# MIXR_Power_-_Battery_Management.net
KiCad netlist of a schematic drawn in Altium Designer
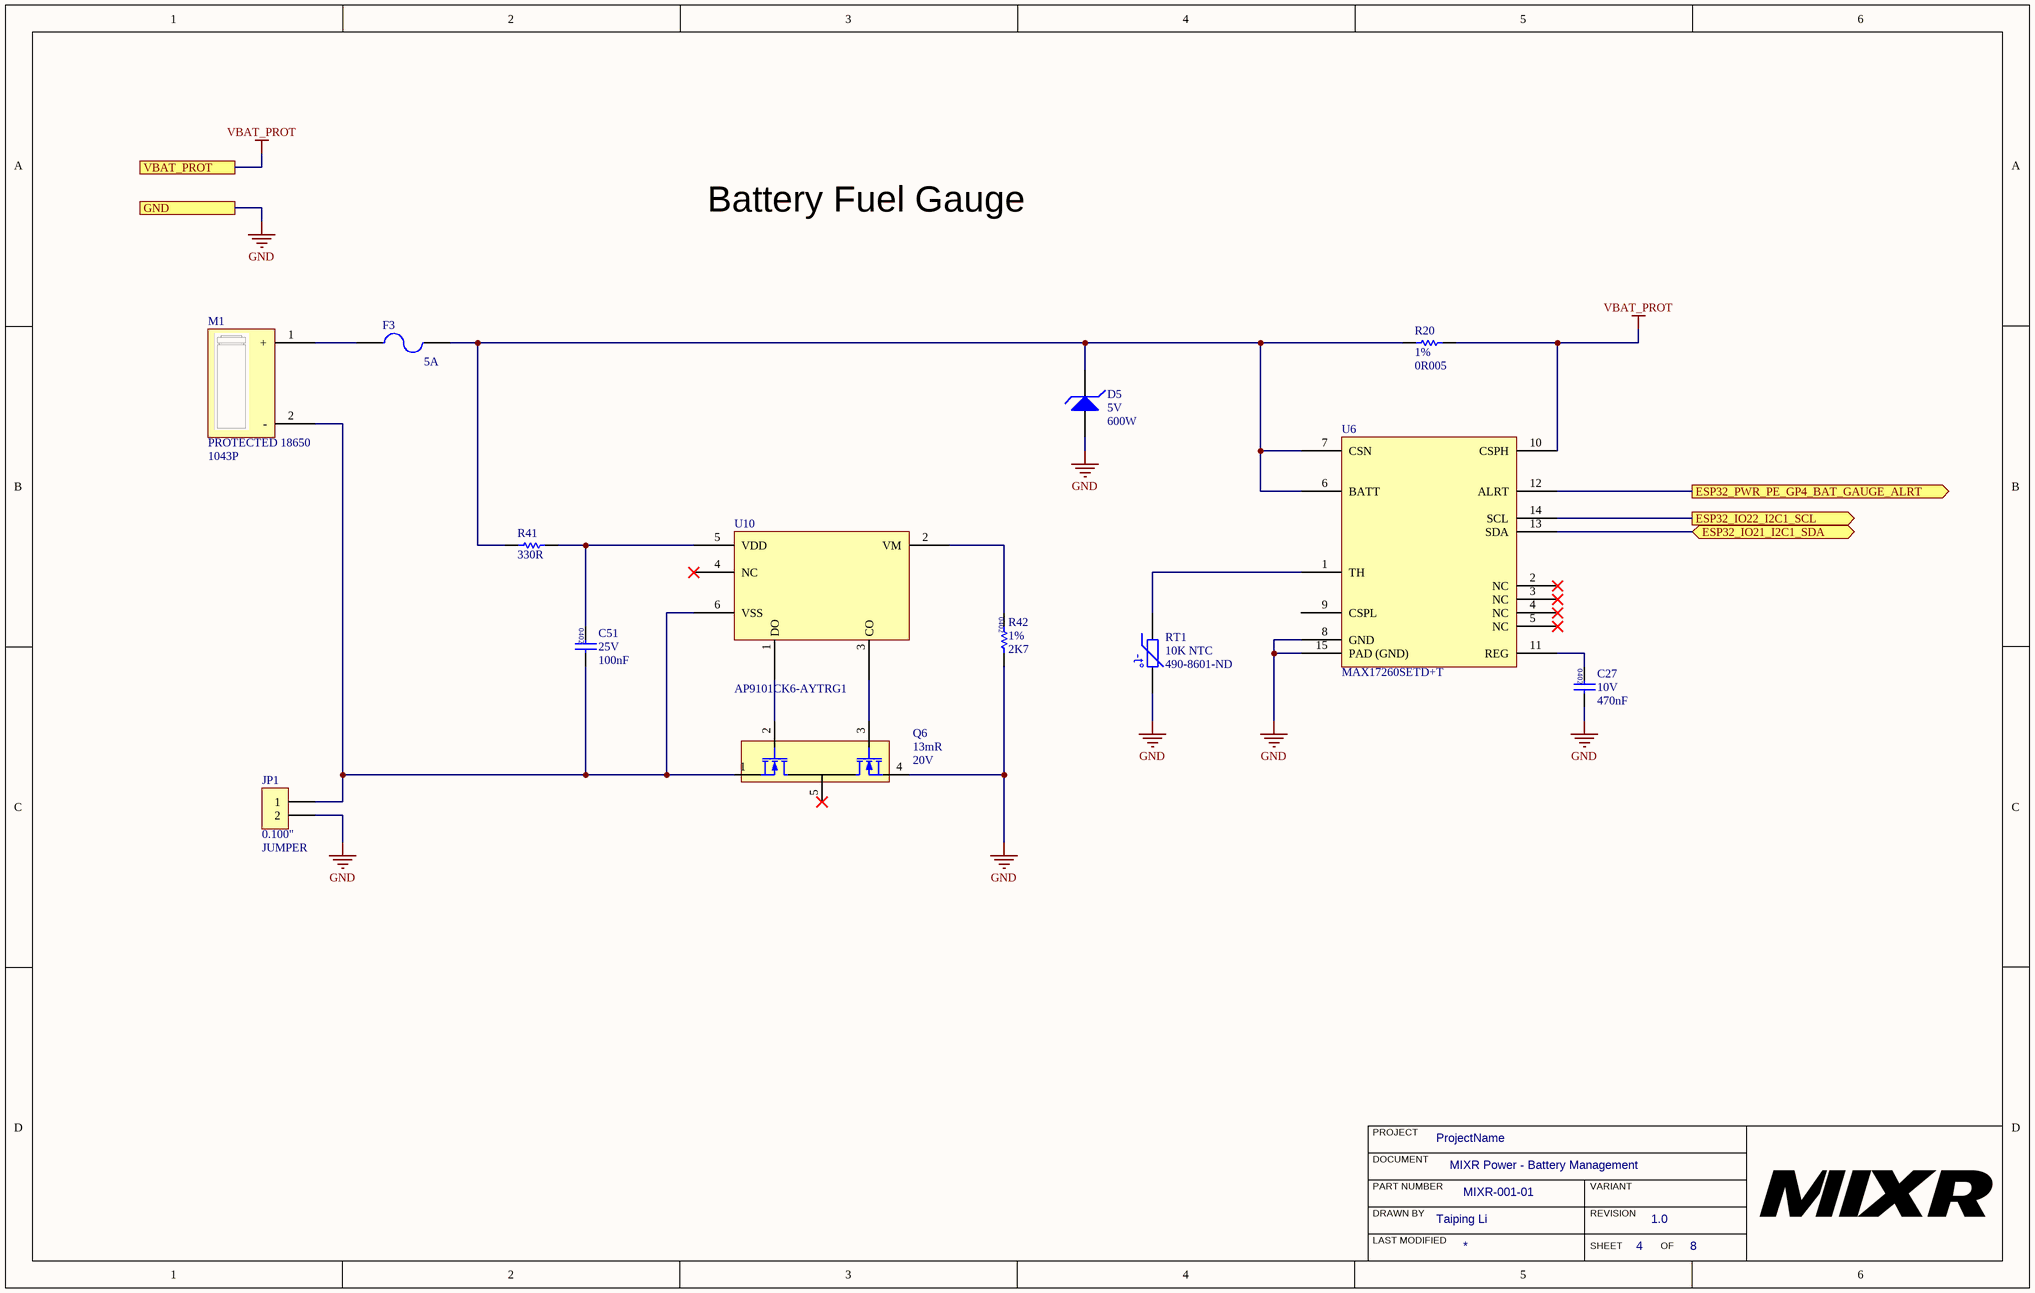
[diagram p0: MIXR Power - Battery Management.SchDoc]

(export (version "E")
  (design (tool "Eeschema 10.0.6"))
  (components
    (comp (ref "C27")
      (value "CAP CER 0.47UF 10V X7R 0402")
      (footprint "CAP 0402")
      (description "CAP ,MLCC ,0402,6.3V,X7R,0.47uF, 10% ,T&R;")
      (fields
        (field (name "MANUFACTURER") "Taiyo Yuden")
        (field (name "MANUFACTURER PART NUMBER") "LMK105B7474KV-F")
        (field (name "VOLTAGE RATING") "10V")
        (field (name "CAPACITANCE") "470nF")
      )
      (libsource (lib "Schematic Diagrams") (part "CAP CER 0.47UF 10V X7R 0402"))
    )
    (comp (ref "C51")
      (value "CAP CER 0.1UF 16V X7R 0402")
      (footprint "CAP 0402")
      (description "Cap Ceramic 0.1uF 25V X7R 10% SMD 0402 125C Paper T/R")
      (fields
        (field (name "MANUFACTURER") "Murata")
        (field (name "MANUFACTURER PART NUMBER") "GRM155R71E104KE14D")
        (field (name "VOLTAGE") "25V")
        (field (name "CAPACITANCE") "100nF")
      )
      (libsource (lib "Schematic Diagrams") (part "CAP CER 0.1UF 16V X7R 0402"))
    )
    (comp (ref "D5")
      (value "DIODE TVS 5VWM 9.1VC DO-214AA (SMB)")
      (footprint "DO-214AA Diode")
      (description "TVS DIODE 5V 9.1V DO214AA")
      (fields
        (field (name "MANUFACTURER") "Vishay Semiconductor Diodes Division")
        (field (name "MANUFACTURER PART NUMBER") "SMBJ5.0D-M3/H")
        (field (name "VOLTAGE - REVERSE STANDOFF (TYP)") "5V")
        (field (name "POWER - PEAK PULSE") "600W")
      )
      (libsource (lib "Schematic Diagrams") (part "DIODE TVS 5VWM 9.1VC DO-214AA (SMB)"))
    )
    (comp (ref "F3")
      (value "FUSE 5A 32VDC 1206")
      (footprint "FUSE LITTLEFUSE 0466 1206")
      (description "FUSE 5.0A 125VAC FAST 1206")
      (fields
        (field (name "MANUFACTURER") "Bel TRP")
        (field (name "MANUFACTURER PART NUMBER") "C1F5")
        (field (name "CURRENT RATING") "5A")
      )
      (libsource (lib "Schematic Diagrams") (part "FUSE 5A 32VDC 1206"))
    )
    (comp (ref "JP1")
      (value "JUMPER")
      (footprint "CONN, 2POS JUMPER 0.1\"")
      (description "2 Positions Header Connector Through Hole Gold")
      (fields
        (field (name "MANUFACTURER") "Omron Electronics Inc-EMC Div")
        (field (name "MANUFACTURER PART NUMBER") "XG8T-0231")
        (field (name "ROW SPACING - MATING") "0.100\"")
        (field (name "TYPE") "JUMPER")
      )
      (libsource (lib "Schematic Diagrams") (part "CONN 2POS JUMPER 0.1{dblquote}"))
    )
    (comp (ref "M1")
      (value "PROTECTED 18650")
      (footprint "BATTERY HOLDER 18650 PC PIN")
      (description "BATTERY HOLDER 18650 PC PIN")
      (fields
        (field (name "MANUFACTURER") "Keystone Electronics")
        (field (name "MANUFACTURER PART NUMBER") "1043P")
      )
      (libsource (lib "Schematic Diagrams") (part "BATTERY HOLDER 18650"))
    )
    (comp (ref "Q6")
      (value "MOSFET 2N-CH 20V 9A 6-UDFN")
      (footprint "MOSFET 2N-CH 6-UDFN")
      (fields
        (field (name "MANUFACTURER") "Diodes")
        (field (name "MANUFACTURER PART NUMBER") "DMN2014LHAB-7")
        (field (name "RDS ON MAX") "13mR")
        (field (name "DRAIN TO SOURCE VOLTAGE (VDSS)") "20V")
      )
      (libsource (lib "Schematic Diagrams") (part "MOSFET 2N-CH 20V 9A 6-UDFN"))
    )
    (comp (ref "R20")
      (value "RES 0.005 OHM 1% 1/2W 0805")
      (footprint "RES CRF0805")
      (fields
        (field (name "MANUFACTURER") "Bourns")
        (field (name "MANUFACTURER PART NUMBER") "CRF0805-FZ-R005ELF")
        (field (name "TOLERANCE") "1%")
        (field (name "RESISTANCE") "0R005")
      )
      (libsource (lib "Schematic Diagrams") (part "RES 0.005 OHM 1% 1/2W 0805"))
    )
    (comp (ref "R41")
      (value "RES 330 OHM 1% 1/10W 0603")
      (footprint "RES, 0603")
      (fields
        (field (name "MANUFACTURER") "TE Connectivity")
        (field (name "MANUFACTURER PART NUMBER") "330R")
      )
      (libsource (lib "Schematic Diagrams") (part "RES 330 OHM 1% 1/10W 0603"))
    )
    (comp (ref "R42")
      (value "RES 2.7K OHM 1% 1/16W 0402")
      (footprint "RES 0402")
      (description "2.7 kOhms ±1% 0.1W, 1/10W Chip Resistor 0402 (1005 Metric) Automotive AEC-Q200 Thick Film")
      (fields
        (field (name "MANUFACTURER") "Panasonic")
        (field (name "MANUFACTURER PART NUMBER") "ERJ-2RKF2701X")
        (field (name "TOLERANCE") "1%")
        (field (name "RESISTANCE") "2K7")
      )
      (libsource (lib "Schematic Diagrams") (part "RES 2.7K OHM 1% 1/16W 0402"))
    )
    (comp (ref "RT1")
      (value "10K NTC")
      (footprint "NTC THERMISTOR BEAD")
      (description "NTC Thermistor 10k Bead")
      (fields
        (field (name "MANUFACTURER") "Murata Electronics North America")
        (field (name "MANUFACTURER PART NUMBER") "NXRT15XH103FA1B030")
        (field (name "SUPPLIER PART NUMBER 1") "490-8601-ND")
      )
      (libsource (lib "Schematic Diagrams") (part "NTC THERMISTOR 10K 1% BEAD"))
    )
    (comp (ref "U6")
      (value "IC BATT FUEL GAUGE LI-ION 14-DFN")
      (footprint "QFN40P300X300X80_HS-15M")
      (fields
        (field (name "MANUFACTURER") "Maxim")
        (field (name "MANUFACTURER PART NUMBER") "MAX17260SETD+T")
      )
      (libsource (lib "Schematic Diagrams") (part "IC BATT FUEL GAUGE LI-ION 14-DFN"))
    )
    (comp (ref "U10")
      (value "IC BATT PROT LI-ION 1-CELL SOT26")
      (footprint "SOT23-6")
      (description "Battery Battery Protection IC Lithium Ion/Polymer SOT-26")
      (fields
        (field (name "MANUFACTURER") "Diodes")
        (field (name "MANUFACTURER PART NUMBER") "AP9101CK6-AYTRG1")
      )
      (libsource (lib "Schematic Diagrams") (part "IC BATT PROT LI-ION 1-CELL SOT26"))
    )
  )
  (nets
    (net (code "1") (name "/ESP32_IO21_I2C1_SDA") (class "Default")
      (node (ref "U6") (pin "13") (pinfunction "SDA_13") (pintype "passive"))
    )
    (net (code "2") (name "/ESP32_IO22_I2C1_SCL") (class "Default")
      (node (ref "U6") (pin "14") (pinfunction "SCL_14") (pintype "passive"))
    )
    (net (code "3") (name "/ESP32_PWR_PE_GP4_BAT_GAUGE_ALRT") (class "Default")
      (node (ref "U6") (pin "12") (pinfunction "ALRT_12") (pintype "passive"))
    )
    (net (code "4") (name "GND") (class "Default")
      (node (ref "C27") (pin "2") (pinfunction "2_2") (pintype "passive"))
      (node (ref "D5") (pin "1") (pinfunction "1_1") (pintype "passive"))
      (node (ref "JP1") (pin "2") (pinfunction "2_2") (pintype "passive"))
      (node (ref "Q6") (pin "4") (pinfunction "S2_4") (pintype "passive"))
      (node (ref "R42") (pin "2") (pinfunction "2_2") (pintype "passive"))
      (node (ref "RT1") (pin "2") (pinfunction "2_2") (pintype "passive"))
      (node (ref "U6") (pin "15") (pinfunction "PAD_(GND)_15") (pintype "passive"))
      (node (ref "U6") (pin "8") (pinfunction "GND_8") (pintype "passive"))
    )
    (net (code "5") (name "Net-(M1-+)") (class "Default")
      (node (ref "F3") (pin "1") (pinfunction "1_1") (pintype "passive"))
      (node (ref "M1") (pin "1") (pinfunction "+_1") (pintype "passive"))
    )
    (net (code "6") (name "Net-(M1--)") (class "Default")
      (node (ref "C51") (pin "2") (pinfunction "2_2") (pintype "passive"))
      (node (ref "JP1") (pin "1") (pinfunction "1_1") (pintype "passive"))
      (node (ref "M1") (pin "2") (pinfunction "-_2") (pintype "passive"))
      (node (ref "Q6") (pin "1") (pinfunction "S1_1") (pintype "passive"))
      (node (ref "U10") (pin "6") (pinfunction "VSS_6") (pintype "passive"))
    )
    (net (code "7") (name "Net-(Q6-G1)") (class "Default")
      (node (ref "Q6") (pin "2") (pinfunction "G1_2") (pintype "passive"))
      (node (ref "U10") (pin "1") (pinfunction "DO_1") (pintype "passive"))
    )
    (net (code "8") (name "Net-(Q6-G2)") (class "Default")
      (node (ref "Q6") (pin "3") (pinfunction "G2_3") (pintype "passive"))
      (node (ref "U10") (pin "3") (pinfunction "CO_3") (pintype "passive"))
    )
    (net (code "9") (name "Net-(U6-BATT)") (class "Default")
      (node (ref "D5") (pin "2") (pinfunction "2_2") (pintype "passive"))
      (node (ref "F3") (pin "2") (pinfunction "2_2") (pintype "passive"))
      (node (ref "R20") (pin "1") (pinfunction "1_1") (pintype "passive"))
      (node (ref "R41") (pin "1") (pinfunction "1_1") (pintype "passive"))
      (node (ref "U6") (pin "6") (pinfunction "BATT_6") (pintype "passive"))
      (node (ref "U6") (pin "7") (pinfunction "CSN_7") (pintype "passive"))
    )
    (net (code "10") (name "Net-(U6-REG)") (class "Default")
      (node (ref "C27") (pin "1") (pinfunction "1_1") (pintype "passive"))
      (node (ref "U6") (pin "11") (pinfunction "REG_11") (pintype "passive"))
    )
    (net (code "11") (name "Net-(U6-TH)") (class "Default")
      (node (ref "RT1") (pin "1") (pinfunction "1_1") (pintype "passive"))
      (node (ref "U6") (pin "1") (pinfunction "TH_1") (pintype "passive"))
    )
    (net (code "12") (name "Net-(U10-VDD)") (class "Default")
      (node (ref "C51") (pin "1") (pinfunction "1_1") (pintype "passive"))
      (node (ref "R41") (pin "2") (pinfunction "2_2") (pintype "passive"))
      (node (ref "U10") (pin "5") (pinfunction "VDD_5") (pintype "passive"))
    )
    (net (code "13") (name "Net-(U10-VM)") (class "Default")
      (node (ref "R42") (pin "1") (pinfunction "1_1") (pintype "passive"))
      (node (ref "U10") (pin "2") (pinfunction "VM_2") (pintype "passive"))
    )
    (net (code "14") (name "VBAT_PROT") (class "Default")
      (node (ref "R20") (pin "2") (pinfunction "2_2") (pintype "passive"))
      (node (ref "U6") (pin "10") (pinfunction "CSPH_10") (pintype "passive"))
    )
    (net (code "15") (name "unconnected-(Q6-D-Pad5)") (class "Default")
      (node (ref "Q6") (pin "5") (pinfunction "D_5") (pintype "passive+no_connect"))
    )
    (net (code "16") (name "unconnected-(U6-CSPL-Pad9)") (class "Default")
      (node (ref "U6") (pin "9") (pinfunction "CSPL_9") (pintype "passive"))
    )
    (net (code "17") (name "unconnected-(U6-NC-Pad2)") (class "Default")
      (node (ref "U6") (pin "2") (pinfunction "NC_2") (pintype "passive+no_connect"))
    )
    (net (code "18") (name "unconnected-(U6-NC-Pad3)") (class "Default")
      (node (ref "U6") (pin "3") (pinfunction "NC_3") (pintype "passive+no_connect"))
    )
    (net (code "19") (name "unconnected-(U6-NC-Pad4)") (class "Default")
      (node (ref "U6") (pin "4") (pinfunction "NC_4") (pintype "passive+no_connect"))
    )
    (net (code "20") (name "unconnected-(U6-NC-Pad5)") (class "Default")
      (node (ref "U6") (pin "5") (pinfunction "NC_5") (pintype "passive+no_connect"))
    )
    (net (code "21") (name "unconnected-(U10-NC-Pad4)") (class "Default")
      (node (ref "U10") (pin "4") (pinfunction "NC_4") (pintype "passive+no_connect"))
    )
  )
)
